# MSP_Lunchbox_OpenSource_v1.net
KiCad netlist of a schematic drawn in EAGLE
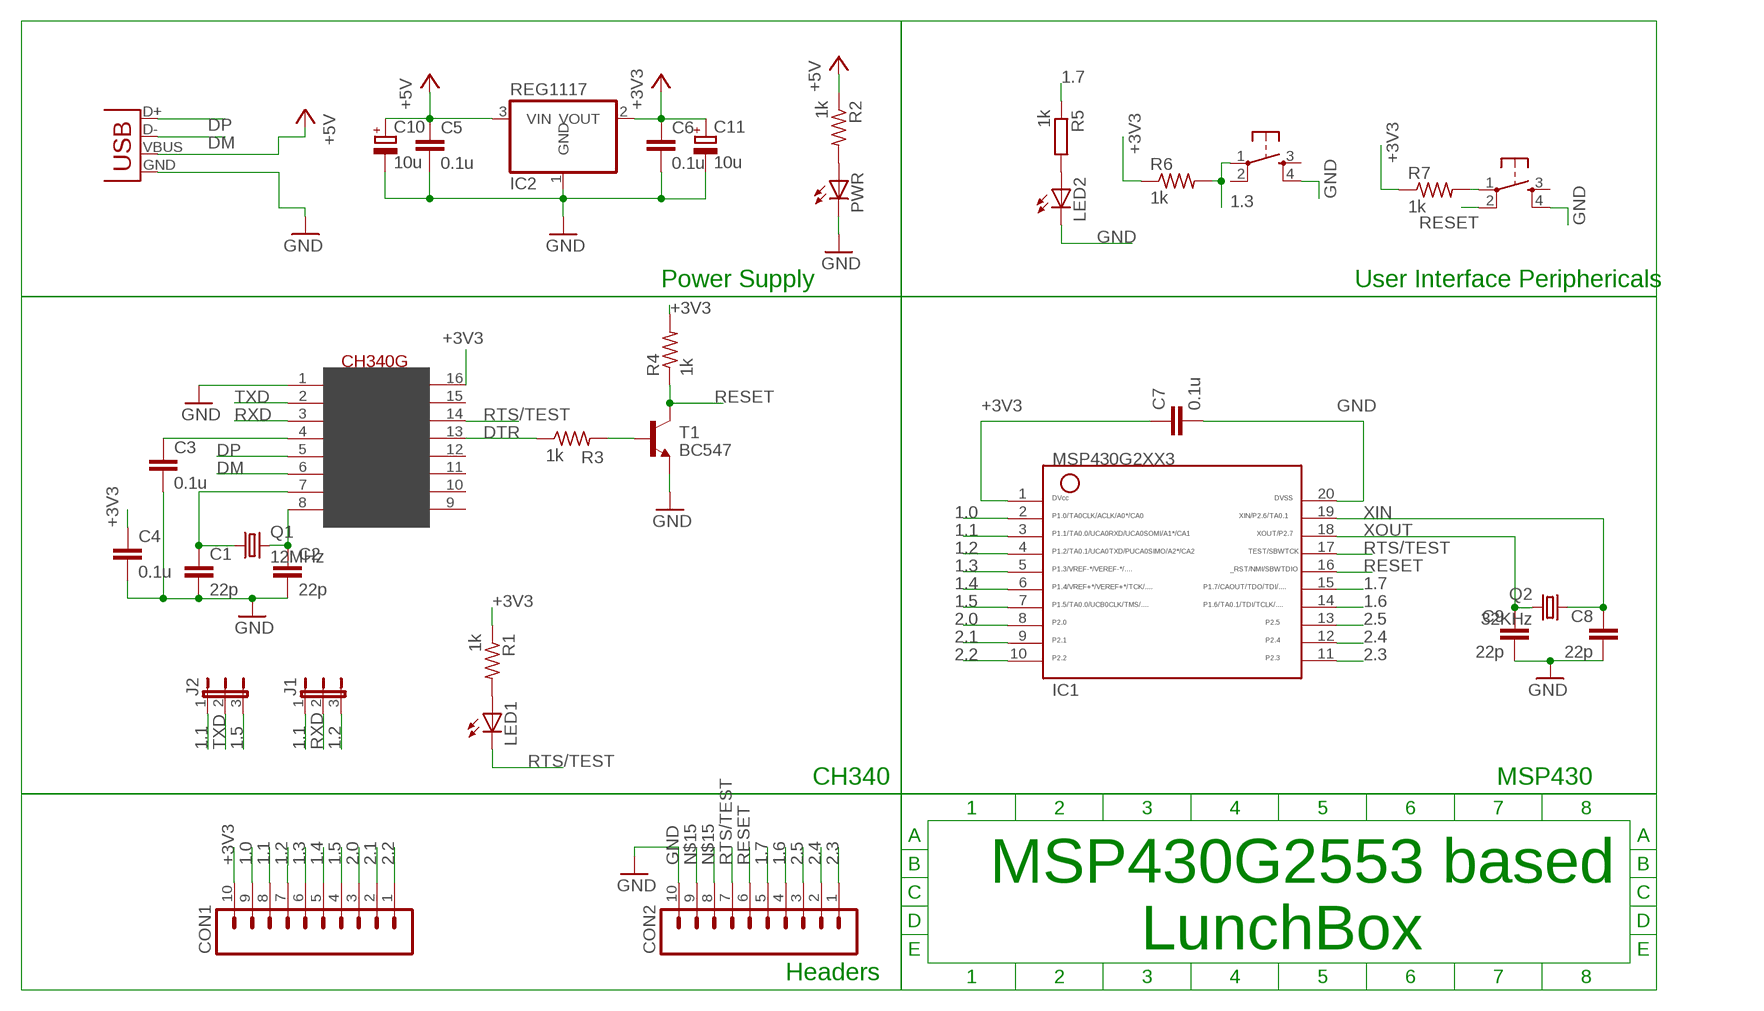
[diagram p0: schematic, sheet 1]

(export (version "E")
  (design (tool "Eeschema 10.0.6"))
  (components
    (comp (ref "C1")
      (value "22p")
      (footprint "eagle-import:C0805")
      (libsource (lib "eagle-import") (part "C-EUC0805"))
    )
    (comp (ref "C2")
      (value "22p")
      (footprint "eagle-import:C0805")
      (libsource (lib "eagle-import") (part "C-EUC0805"))
    )
    (comp (ref "C3")
      (value "0.1u")
      (footprint "eagle-import:C0805")
      (libsource (lib "eagle-import") (part "C-EUC0805"))
    )
    (comp (ref "C4")
      (value "0.1u")
      (footprint "eagle-import:C0805")
      (libsource (lib "eagle-import") (part "C-EUC0805"))
    )
    (comp (ref "C5")
      (value "0.1u")
      (footprint "eagle-import:C0805")
      (libsource (lib "eagle-import") (part "C-EUC0805"))
    )
    (comp (ref "C6")
      (value "0.1u")
      (footprint "eagle-import:C0805")
      (libsource (lib "eagle-import") (part "C-EUC0805"))
    )
    (comp (ref "C7")
      (value "0.1u")
      (footprint "eagle-import:C075-032X103")
      (libsource (lib "eagle-import") (part "C-EU075-032X103"))
    )
    (comp (ref "C8")
      (value "22p")
      (footprint "eagle-import:C0805")
      (libsource (lib "eagle-import") (part "C-EUC0805"))
    )
    (comp (ref "C9")
      (value "22p")
      (footprint "eagle-import:C0805")
      (libsource (lib "eagle-import") (part "C-EUC0805"))
    )
    (comp (ref "C10")
      (value "10u")
      (footprint "eagle-import:B_3528-21R")
      (libsource (lib "eagle-import") (part "CPOL-EUB/3528-21R"))
    )
    (comp (ref "C11")
      (value "10u")
      (footprint "eagle-import:B_3528-21R")
      (libsource (lib "eagle-import") (part "CPOL-EUB/3528-21R"))
    )
    (comp (ref "CH340")
      (value "CH340")
      (footprint "eagle-import:SOIC16")
      (libsource (lib "eagle-import") (part "CH340G"))
    )
    (comp (ref "CON1")
      (value "M10")
      (footprint "eagle-import:10P")
      (libsource (lib "eagle-import") (part "M10"))
    )
    (comp (ref "CON2")
      (value "M10")
      (footprint "eagle-import:10P")
      (libsource (lib "eagle-import") (part "M10"))
    )
    (comp (ref "IC1")
      (value "MSP430G2553DIP20")
      (footprint "eagle-import:G2553-DIP20")
      (libsource (lib "eagle-import") (part "MSP430G2553DIP20"))
    )
    (comp (ref "IC2")
      (value "REG1117")
      (footprint "eagle-import:SOT223")
      (libsource (lib "eagle-import") (part "REG1117"))
    )
    (comp (ref "J1")
      (value "JP2E")
      (footprint "eagle-import:JP2")
      (libsource (lib "eagle-import") (part "JP2E"))
    )
    (comp (ref "J2")
      (value "JP2E")
      (footprint "eagle-import:JP2")
      (libsource (lib "eagle-import") (part "JP2E"))
    )
    (comp (ref "LED1")
      (value "LED3MM")
      (footprint "eagle-import:LED3MM")
      (libsource (lib "eagle-import") (part "LED3MM"))
    )
    (comp (ref "LED2")
      (value "LED3MM")
      (footprint "eagle-import:LED3MM")
      (libsource (lib "eagle-import") (part "LED3MM"))
    )
    (comp (ref "PWR")
      (value "LED3MM")
      (footprint "eagle-import:LED3MM")
      (libsource (lib "eagle-import") (part "LED3MM"))
    )
    (comp (ref "Q1")
      (value "12MHz")
      (footprint "eagle-import:HC49US")
      (libsource (lib "eagle-import") (part "CRYSTALHC49US"))
    )
    (comp (ref "Q2")
      (value "32KHz")
      (footprint "eagle-import:TC26H")
      (libsource (lib "eagle-import") (part "CEDT_JANUARY_2015_v5_CRYSTALTC26H"))
    )
    (comp (ref "R1")
      (value "1k")
      (footprint "eagle-import:0207_10")
      (libsource (lib "eagle-import") (part "R-US_0207/10"))
    )
    (comp (ref "R2")
      (value "1k")
      (footprint "eagle-import:0207_10")
      (libsource (lib "eagle-import") (part "R-US_0207/10"))
    )
    (comp (ref "R3")
      (value "1k")
      (footprint "eagle-import:0207_10")
      (libsource (lib "eagle-import") (part "R-US_0207/10"))
    )
    (comp (ref "R4")
      (value "1k")
      (footprint "eagle-import:0207_10")
      (libsource (lib "eagle-import") (part "R-US_0207/10"))
    )
    (comp (ref "R5")
      (value "1k")
      (footprint "eagle-import:0207_12")
      (libsource (lib "eagle-import") (part "R-EU_0207/12"))
    )
    (comp (ref "R6")
      (value "1k")
      (footprint "eagle-import:0204_7")
      (libsource (lib "eagle-import") (part "R-US_0204/7"))
    )
    (comp (ref "R7")
      (value "1k")
      (footprint "eagle-import:0204_7")
      (libsource (lib "eagle-import") (part "R-US_0204/7"))
    )
    (comp (ref "RESET")
      (value "OMRON_SWITCH_10-XX")
      (footprint "eagle-import:B3F-10XX")
      (libsource (lib "eagle-import") (part "OMRON_SWITCH_10-XX"))
    )
    (comp (ref "SW1")
      (value "OMRON_SWITCH_10-XX")
      (footprint "eagle-import:B3F-10XX")
      (libsource (lib "eagle-import") (part "OMRON_SWITCH_10-XX"))
    )
    (comp (ref "T1")
      (value "BC547")
      (footprint "eagle-import:TO92")
      (libsource (lib "eagle-import") (part "BC547"))
    )
    (comp (ref "X2")
      (value "USBSMD")
      (footprint "eagle-import:USB-MINIB")
      (libsource (lib "eagle-import") (part "USBSMD"))
    )
  )
  (nets
    (net (code "1") (name "+3V3") (class "Default")
      (node (ref "C11") (pin "+") (pinfunction "+_+") (pintype "passive"))
      (node (ref "C4") (pin "1") (pinfunction "1_1") (pintype "passive"))
      (node (ref "C6") (pin "1") (pinfunction "1_1") (pintype "passive"))
      (node (ref "C7") (pin "1") (pinfunction "1_1") (pintype "passive"))
      (node (ref "CH340") (pin "16") (pinfunction "VCC_16") (pintype "bidirectional"))
      (node (ref "CON1") (pin "10") (pinfunction "10_10") (pintype "passive"))
      (node (ref "IC1") (pin "1") (pinfunction "1_1") (pintype "power_in"))
      (node (ref "IC2") (pin "2") (pinfunction "VOUT_2") (pintype "output"))
      (node (ref "R1") (pin "1") (pinfunction "1_1") (pintype "passive"))
      (node (ref "R4") (pin "2") (pinfunction "2_2") (pintype "passive"))
      (node (ref "R6") (pin "1") (pinfunction "1_1") (pintype "passive"))
      (node (ref "R7") (pin "1") (pinfunction "1_1") (pintype "passive"))
    )
    (net (code "2") (name "+5V") (class "Default")
      (node (ref "C10") (pin "+") (pinfunction "+_+") (pintype "passive"))
      (node (ref "C5") (pin "1") (pinfunction "1_1") (pintype "passive"))
      (node (ref "IC2") (pin "3") (pinfunction "VIN_3") (pintype "input"))
      (node (ref "R2") (pin "1") (pinfunction "1_1") (pintype "passive"))
      (node (ref "X2") (pin "VBUS") (pinfunction "VBUS_VBUS") (pintype "bidirectional"))
    )
    (net (code "3") (name "/1.0") (class "Default")
      (node (ref "CON1") (pin "9") (pinfunction "9_9") (pintype "passive"))
      (node (ref "IC1") (pin "2") (pinfunction "2_2") (pintype "bidirectional"))
    )
    (net (code "4") (name "/1.1") (class "Default")
      (node (ref "CON1") (pin "8") (pinfunction "8_8") (pintype "passive"))
      (node (ref "IC1") (pin "3") (pinfunction "3_3") (pintype "bidirectional"))
      (node (ref "J1") (pin "1") (pinfunction "1_1") (pintype "passive"))
      (node (ref "J2") (pin "1") (pinfunction "1_1") (pintype "passive"))
    )
    (net (code "5") (name "/1.2") (class "Default")
      (node (ref "CON1") (pin "7") (pinfunction "7_7") (pintype "passive"))
      (node (ref "IC1") (pin "4") (pinfunction "4_4") (pintype "bidirectional"))
      (node (ref "J1") (pin "3") (pinfunction "3_3") (pintype "passive"))
    )
    (net (code "6") (name "/1.3") (class "Default")
      (node (ref "CON1") (pin "6") (pinfunction "6_6") (pintype "passive"))
      (node (ref "IC1") (pin "5") (pinfunction "5_5") (pintype "bidirectional"))
      (node (ref "R6") (pin "2") (pinfunction "2_2") (pintype "passive"))
      (node (ref "SW1") (pin "1") (pinfunction "P_1") (pintype "passive"))
    )
    (net (code "7") (name "/1.4") (class "Default")
      (node (ref "CON1") (pin "5") (pinfunction "5_5") (pintype "passive"))
      (node (ref "IC1") (pin "6") (pinfunction "6_6") (pintype "bidirectional"))
    )
    (net (code "8") (name "/1.5") (class "Default")
      (node (ref "CON1") (pin "4") (pinfunction "4_4") (pintype "passive"))
      (node (ref "IC1") (pin "7") (pinfunction "7_7") (pintype "bidirectional"))
      (node (ref "J2") (pin "3") (pinfunction "3_3") (pintype "passive"))
    )
    (net (code "9") (name "/1.6") (class "Default")
      (node (ref "CON2") (pin "4") (pinfunction "4_4") (pintype "passive"))
      (node (ref "IC1") (pin "14") (pinfunction "14_14") (pintype "bidirectional"))
    )
    (net (code "10") (name "/1.7") (class "Default")
      (node (ref "CON2") (pin "5") (pinfunction "5_5") (pintype "passive"))
      (node (ref "IC1") (pin "15") (pinfunction "15_15") (pintype "bidirectional"))
      (node (ref "R5") (pin "1") (pinfunction "1_1") (pintype "passive"))
    )
    (net (code "11") (name "/2.0") (class "Default")
      (node (ref "CON1") (pin "3") (pinfunction "3_3") (pintype "passive"))
      (node (ref "IC1") (pin "8") (pinfunction "8_8") (pintype "bidirectional"))
    )
    (net (code "12") (name "/2.1") (class "Default")
      (node (ref "CON1") (pin "2") (pinfunction "2_2") (pintype "passive"))
      (node (ref "IC1") (pin "9") (pinfunction "9_9") (pintype "bidirectional"))
    )
    (net (code "13") (name "/2.2") (class "Default")
      (node (ref "CON1") (pin "1") (pinfunction "1_1") (pintype "passive"))
      (node (ref "IC1") (pin "10") (pinfunction "10_10") (pintype "bidirectional"))
    )
    (net (code "14") (name "/2.3") (class "Default")
      (node (ref "CON2") (pin "1") (pinfunction "1_1") (pintype "passive"))
      (node (ref "IC1") (pin "11") (pinfunction "11_11") (pintype "bidirectional"))
    )
    (net (code "15") (name "/2.4") (class "Default")
      (node (ref "CON2") (pin "2") (pinfunction "2_2") (pintype "passive"))
      (node (ref "IC1") (pin "12") (pinfunction "12_12") (pintype "bidirectional"))
    )
    (net (code "16") (name "/2.5") (class "Default")
      (node (ref "CON2") (pin "3") (pinfunction "3_3") (pintype "passive"))
      (node (ref "IC1") (pin "13") (pinfunction "13_13") (pintype "bidirectional"))
    )
    (net (code "17") (name "/DM") (class "Default")
      (node (ref "CH340") (pin "6") (pinfunction "D-_6") (pintype "bidirectional"))
      (node (ref "X2") (pin "D-") (pinfunction "D-_D-") (pintype "bidirectional"))
    )
    (net (code "18") (name "/DP") (class "Default")
      (node (ref "CH340") (pin "5") (pinfunction "D+_5") (pintype "bidirectional"))
      (node (ref "X2") (pin "D+") (pinfunction "D+_D+") (pintype "bidirectional"))
    )
    (net (code "19") (name "/DTR") (class "Default")
      (node (ref "CH340") (pin "13") (pinfunction "DTR_13") (pintype "bidirectional"))
      (node (ref "R3") (pin "1") (pinfunction "1_1") (pintype "passive"))
    )
    (net (code "20") (name "/N$15") (class "Default")
      (node (ref "CON2") (pin "8") (pinfunction "8_8") (pintype "passive"))
    )
    (net (code "21") (name "/RESET") (class "Default")
      (node (ref "CON2") (pin "6") (pinfunction "6_6") (pintype "passive"))
      (node (ref "IC1") (pin "16") (pinfunction "16_16") (pintype "bidirectional"))
      (node (ref "R4") (pin "1") (pinfunction "1_1") (pintype "passive"))
      (node (ref "RESET") (pin "2") (pinfunction "P1_2") (pintype "passive"))
      (node (ref "T1") (pin "3") (pinfunction "C_3") (pintype "passive"))
    )
    (net (code "22") (name "/RTS{slash}TEST") (class "Default")
      (node (ref "CH340") (pin "14") (pinfunction "RTS_14") (pintype "bidirectional"))
      (node (ref "CON2") (pin "7") (pinfunction "7_7") (pintype "passive"))
      (node (ref "IC1") (pin "17") (pinfunction "17_17") (pintype "bidirectional"))
      (node (ref "LED1") (pin "K") (pinfunction "C_K") (pintype "passive"))
    )
    (net (code "23") (name "/RXD") (class "Default")
      (node (ref "CH340") (pin "3") (pinfunction "RX_3") (pintype "bidirectional"))
      (node (ref "J1") (pin "2") (pinfunction "2_2") (pintype "passive"))
    )
    (net (code "24") (name "/TXD") (class "Default")
      (node (ref "CH340") (pin "2") (pinfunction "TX_2") (pintype "bidirectional"))
      (node (ref "J2") (pin "2") (pinfunction "2_2") (pintype "passive"))
    )
    (net (code "25") (name "/XIN") (class "Default")
      (node (ref "C8") (pin "1") (pinfunction "1_1") (pintype "passive"))
      (node (ref "IC1") (pin "19") (pinfunction "19_19") (pintype "bidirectional"))
      (node (ref "Q2") (pin "1") (pinfunction "1_1") (pintype "passive"))
    )
    (net (code "26") (name "/XOUT") (class "Default")
      (node (ref "C9") (pin "1") (pinfunction "1_1") (pintype "passive"))
      (node (ref "IC1") (pin "18") (pinfunction "18_18") (pintype "bidirectional"))
      (node (ref "Q2") (pin "2") (pinfunction "2_2") (pintype "passive"))
    )
    (net (code "27") (name "GND") (class "Default")
      (node (ref "C1") (pin "2") (pinfunction "2_2") (pintype "passive"))
      (node (ref "C10") (pin "-") (pinfunction "-_-") (pintype "passive"))
      (node (ref "C11") (pin "-") (pinfunction "-_-") (pintype "passive"))
      (node (ref "C2") (pin "2") (pinfunction "2_2") (pintype "passive"))
      (node (ref "C3") (pin "2") (pinfunction "2_2") (pintype "passive"))
      (node (ref "C4") (pin "2") (pinfunction "2_2") (pintype "passive"))
      (node (ref "C5") (pin "2") (pinfunction "2_2") (pintype "passive"))
      (node (ref "C6") (pin "2") (pinfunction "2_2") (pintype "passive"))
      (node (ref "C7") (pin "2") (pinfunction "2_2") (pintype "passive"))
      (node (ref "C8") (pin "2") (pinfunction "2_2") (pintype "passive"))
      (node (ref "C9") (pin "2") (pinfunction "2_2") (pintype "passive"))
      (node (ref "CH340") (pin "1") (pinfunction "GND_1") (pintype "bidirectional"))
      (node (ref "CON2") (pin "10") (pinfunction "10_10") (pintype "passive"))
      (node (ref "IC1") (pin "20") (pinfunction "20_20") (pintype "power_in"))
      (node (ref "IC2") (pin "1") (pinfunction "GND_1") (pintype "power_in"))
      (node (ref "LED2") (pin "K") (pinfunction "C_K") (pintype "passive"))
      (node (ref "PWR") (pin "K") (pinfunction "C_K") (pintype "passive"))
      (node (ref "RESET") (pin "4") (pinfunction "S1_4") (pintype "passive"))
      (node (ref "SW1") (pin "4") (pinfunction "S1_4") (pintype "passive"))
      (node (ref "T1") (pin "1") (pinfunction "E_1") (pintype "passive"))
      (node (ref "X2") (pin "GND") (pinfunction "GND_GND") (pintype "bidirectional"))
    )
    (net (code "28") (name "Net-(CH340-V3)") (class "Default")
      (node (ref "C3") (pin "1") (pinfunction "1_1") (pintype "passive"))
      (node (ref "CH340") (pin "4") (pinfunction "V3_4") (pintype "bidirectional"))
    )
    (net (code "29") (name "Net-(CH340-XI)") (class "Default")
      (node (ref "C1") (pin "1") (pinfunction "1_1") (pintype "passive"))
      (node (ref "CH340") (pin "7") (pinfunction "XI_7") (pintype "bidirectional"))
      (node (ref "Q1") (pin "1") (pinfunction "1_1") (pintype "passive"))
    )
    (net (code "30") (name "Net-(CH340-XO)") (class "Default")
      (node (ref "C2") (pin "1") (pinfunction "1_1") (pintype "passive"))
      (node (ref "CH340") (pin "8") (pinfunction "XO_8") (pintype "bidirectional"))
      (node (ref "Q1") (pin "2") (pinfunction "2_2") (pintype "passive"))
    )
    (net (code "31") (name "Net-(LED1-PadA)") (class "Default")
      (node (ref "LED1") (pin "A") (pinfunction "A_A") (pintype "passive"))
      (node (ref "R1") (pin "2") (pinfunction "2_2") (pintype "passive"))
    )
    (net (code "32") (name "Net-(LED2-PadA)") (class "Default")
      (node (ref "LED2") (pin "A") (pinfunction "A_A") (pintype "passive"))
      (node (ref "R5") (pin "2") (pinfunction "2_2") (pintype "passive"))
    )
    (net (code "33") (name "Net-(PWR-PadA)") (class "Default")
      (node (ref "PWR") (pin "A") (pinfunction "A_A") (pintype "passive"))
      (node (ref "R2") (pin "2") (pinfunction "2_2") (pintype "passive"))
    )
    (net (code "34") (name "Net-(RESET-P)") (class "Default")
      (node (ref "R7") (pin "2") (pinfunction "2_2") (pintype "passive"))
      (node (ref "RESET") (pin "1") (pinfunction "P_1") (pintype "passive"))
    )
    (net (code "35") (name "Net-(T1-B)") (class "Default")
      (node (ref "R3") (pin "2") (pinfunction "2_2") (pintype "passive"))
      (node (ref "T1") (pin "2") (pinfunction "B_2") (pintype "passive"))
    )
    (net (code "36") (name "unconnected-(CH340-CTS-Pad9)") (class "Default")
      (node (ref "CH340") (pin "9") (pinfunction "CTS_9") (pintype "bidirectional"))
    )
    (net (code "37") (name "unconnected-(CH340-DCD-Pad12)") (class "Default")
      (node (ref "CH340") (pin "12") (pinfunction "DCD_12") (pintype "bidirectional"))
    )
    (net (code "38") (name "unconnected-(CH340-DSR-Pad10)") (class "Default")
      (node (ref "CH340") (pin "10") (pinfunction "DSR_10") (pintype "bidirectional"))
    )
    (net (code "39") (name "unconnected-(CH340-RI-Pad11)") (class "Default")
      (node (ref "CH340") (pin "11") (pinfunction "RI_11") (pintype "bidirectional"))
    )
    (net (code "40") (name "unconnected-(CH340-RS232-Pad15)") (class "Default")
      (node (ref "CH340") (pin "15") (pinfunction "RS232_15") (pintype "bidirectional"))
    )
    (net (code "41") (name "unconnected-(CON2-Pad9)") (class "Default")
      (node (ref "CON2") (pin "9") (pinfunction "9_9") (pintype "passive"))
    )
    (net (code "42") (name "unconnected-(RESET-S-Pad3)") (class "Default")
      (node (ref "RESET") (pin "3") (pinfunction "S_3") (pintype "passive"))
    )
    (net (code "43") (name "unconnected-(SW1-P1-Pad2)") (class "Default")
      (node (ref "SW1") (pin "2") (pinfunction "P1_2") (pintype "passive"))
    )
    (net (code "44") (name "unconnected-(SW1-S-Pad3)") (class "Default")
      (node (ref "SW1") (pin "3") (pinfunction "S_3") (pintype "passive"))
    )
  )
)
